# DualModeKeyboard.net
KiCad netlist of a schematic drawn in EasyEDA Pro
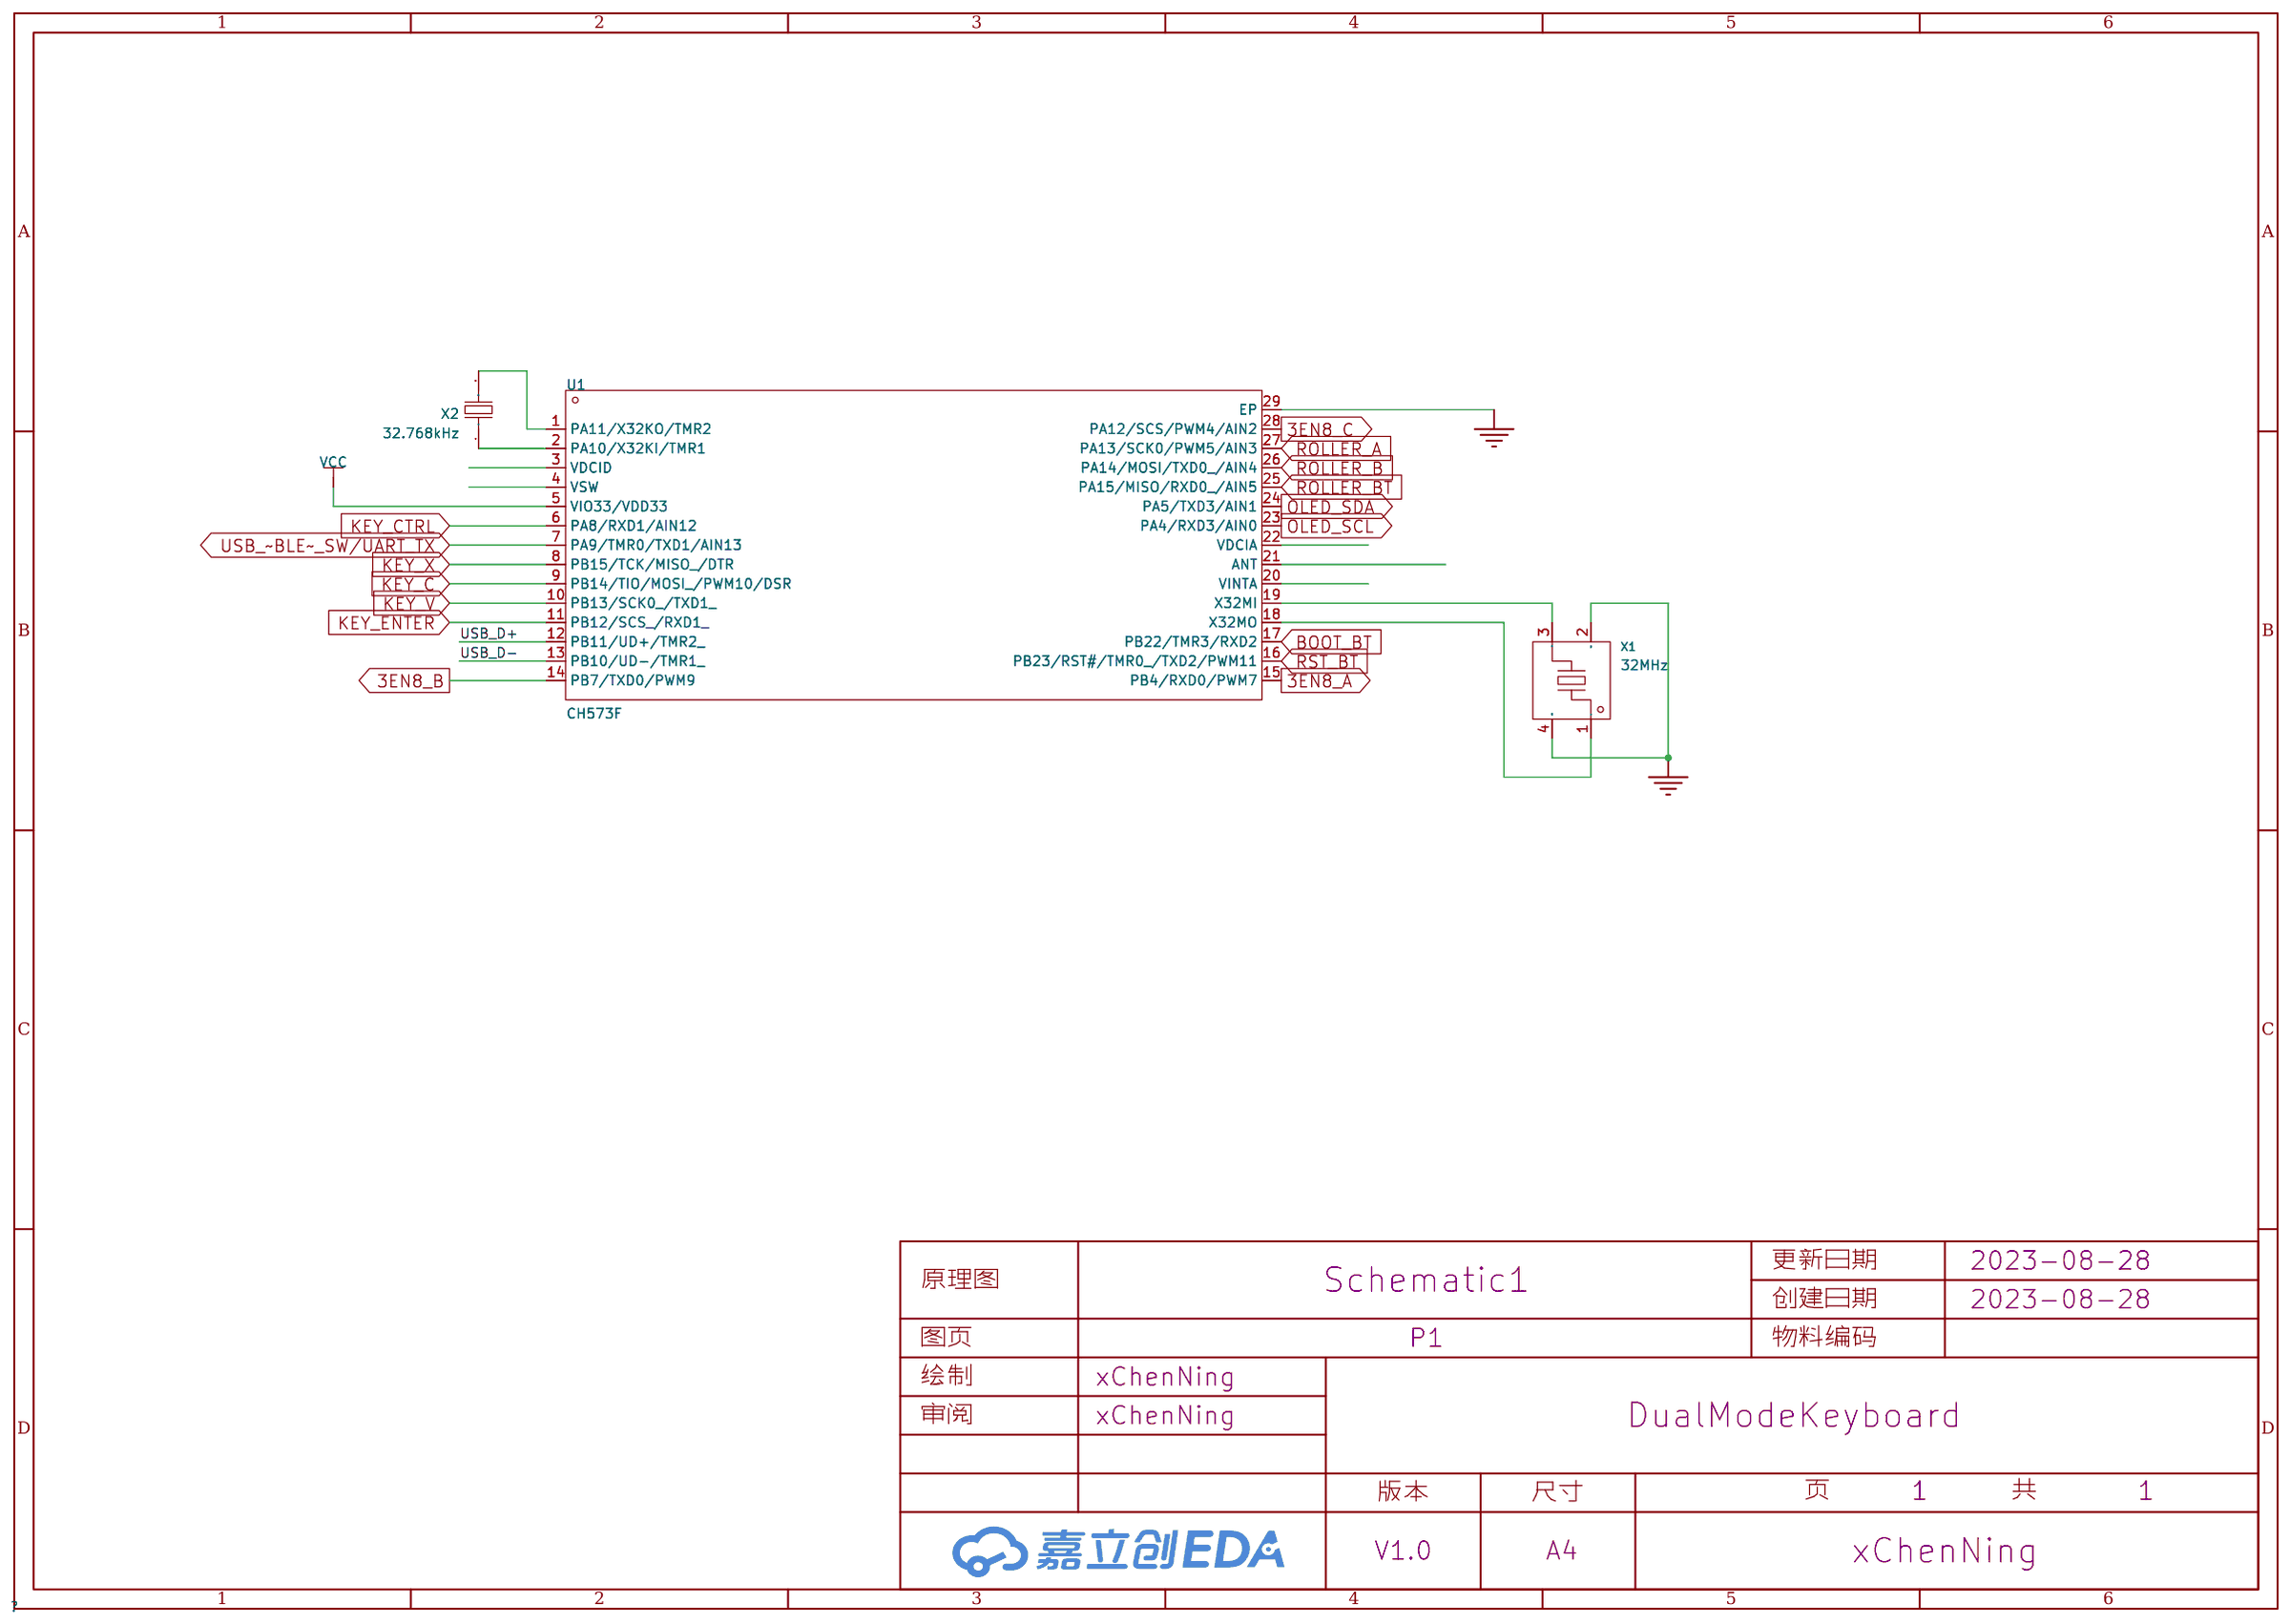
[diagram p0: schematic sheet]

(export (version "E")
  (design (tool "Eeschema 10.0.6"))
  (components
    (comp (ref "U1")
      (value "CH573F")
      (footprint "easyedapro:QFN-28_L4.0-W4.0-P0.40-BL-EP")
      (libsource (lib "easyedapro") (part "CH573F"))
    )
    (comp (ref "X1")
      (value "32MHz")
      (footprint "easyedapro:CRYSTAL-SMD_4P-L2.0-W1.6-BL")
      (description "频率:32MHz;频率公差:±10ppm;负载电容:8pF;")
      (fields (field (name "Manufacturer Part") "Q22FA1280002500") (field (name "Manufacturer") "EPSON(爱普生)"))
      (libsource (lib "easyedapro") (part "Q22FA12800025"))
    )
    (comp (ref "X2")
      (value "32.768kHz")
      (footprint "easyedapro:FC-135R_L3.2-W1.5")
      (description "频率:32.768kHz;频率公差:±20ppm;负载电容:12.5pF;")
      (fields (field (name "Manufacturer Part") "Q13FC1350000400") (field (name "Manufacturer") "EPSON(爱普生)"))
      (libsource (lib "easyedapro") (part "Q13FC1350000400"))
    )
  )
  (nets
    (net (code "1") (name "/USB_D+") (class "Default")
      (node (ref "U1") (pin "12") (pinfunction "PB11/UD+/TMR2__12") (pintype "input"))
    )
    (net (code "2") (name "/USB_D-") (class "Default")
      (node (ref "U1") (pin "13") (pinfunction "PB10/UD-/TMR1__13") (pintype "input"))
    )
    (net (code "3") (name "3EN8_A") (class "Default")
      (node (ref "U1") (pin "15") (pinfunction "PB4/RXD0/PWM7_15") (pintype "input"))
    )
    (net (code "4") (name "3EN8_B") (class "Default")
      (node (ref "U1") (pin "14") (pinfunction "PB7/TXD0/PWM9_14") (pintype "input"))
    )
    (net (code "5") (name "3EN8_C") (class "Default")
      (node (ref "U1") (pin "28") (pinfunction "PA12/SCS/PWM4/AIN2_28") (pintype "input"))
    )
    (net (code "6") (name "BOOT_BT") (class "Default")
      (node (ref "U1") (pin "17") (pinfunction "PB22/TMR3/RXD2_17") (pintype "input"))
    )
    (net (code "7") (name "GND") (class "Default")
      (node (ref "U1") (pin "29") (pinfunction "EP_29") (pintype "input"))
      (node (ref "X1") (pin "2") (pinfunction "GND_2") (pintype "input"))
      (node (ref "X1") (pin "4") (pinfunction "GND_4") (pintype "input"))
    )
    (net (code "8") (name "KEY_C") (class "Default")
      (node (ref "U1") (pin "9") (pinfunction "PB14/TIO/MOSI_/PWM10/DSR_9") (pintype "input"))
    )
    (net (code "9") (name "KEY_CTRL") (class "Default")
      (node (ref "U1") (pin "6") (pinfunction "PA8/RXD1/AIN12_6") (pintype "input"))
    )
    (net (code "10") (name "KEY_ENTER") (class "Default")
      (node (ref "U1") (pin "11") (pinfunction "PB12/SCS_/RXD1__11") (pintype "input"))
    )
    (net (code "11") (name "KEY_V") (class "Default")
      (node (ref "U1") (pin "10") (pinfunction "PB13/SCK0_/TXD1__10") (pintype "input"))
    )
    (net (code "12") (name "KEY_X") (class "Default")
      (node (ref "U1") (pin "8") (pinfunction "PB15/TCK/MISO_/DTR_8") (pintype "input"))
    )
    (net (code "13") (name "Net-(U1-PA10{slash}X32KI{slash}TMR1)") (class "Default")
      (node (ref "U1") (pin "2") (pinfunction "PA10/X32KI/TMR1_2") (pintype "input"))
      (node (ref "X2") (pin "1") (pinfunction "1_1") (pintype "input"))
    )
    (net (code "14") (name "Net-(U1-PA11{slash}X32KO{slash}TMR2)") (class "Default")
      (node (ref "U1") (pin "1") (pinfunction "PA11/X32KO/TMR2_1") (pintype "input"))
      (node (ref "X2") (pin "2") (pinfunction "2_2") (pintype "input"))
    )
    (net (code "15") (name "Net-(U1-X32MI)") (class "Default")
      (node (ref "U1") (pin "19") (pinfunction "X32MI_19") (pintype "input"))
      (node (ref "X1") (pin "3") (pinfunction "3_3") (pintype "input"))
    )
    (net (code "16") (name "Net-(U1-X32MO)") (class "Default")
      (node (ref "U1") (pin "18") (pinfunction "X32MO_18") (pintype "input"))
      (node (ref "X1") (pin "1") (pinfunction "1_1") (pintype "input"))
    )
    (net (code "17") (name "OLED_SCL") (class "Default")
      (node (ref "U1") (pin "23") (pinfunction "PA4/RXD3/AIN0_23") (pintype "input"))
    )
    (net (code "18") (name "OLED_SDA") (class "Default")
      (node (ref "U1") (pin "24") (pinfunction "PA5/TXD3/AIN1_24") (pintype "input"))
    )
    (net (code "19") (name "ROLLER_A") (class "Default")
      (node (ref "U1") (pin "27") (pinfunction "PA13/SCK0/PWM5/AIN3_27") (pintype "input"))
    )
    (net (code "20") (name "ROLLER_B") (class "Default")
      (node (ref "U1") (pin "26") (pinfunction "PA14/MOSI/TXD0_/AIN4_26") (pintype "input"))
    )
    (net (code "21") (name "ROLLER_BT") (class "Default")
      (node (ref "U1") (pin "25") (pinfunction "PA15/MISO/RXD0_/AIN5_25") (pintype "input"))
    )
    (net (code "22") (name "RST_BT") (class "Default")
      (node (ref "U1") (pin "16") (pinfunction "PB23/RST#/TMR0_/TXD2/PWM11_16") (pintype "input"))
    )
    (net (code "23") (name "USB_~BLE~_SW{slash}UART_TX") (class "Default")
      (node (ref "U1") (pin "7") (pinfunction "PA9/TMR0/TXD1/AIN13_7") (pintype "input"))
    )
    (net (code "24") (name "VCC") (class "Default")
      (node (ref "U1") (pin "5") (pinfunction "VIO33/VDD33_5") (pintype "input"))
    )
    (net (code "25") (name "unconnected-(U1-ANT-Pad21)") (class "Default")
      (node (ref "U1") (pin "21") (pinfunction "ANT_21") (pintype "input"))
    )
    (net (code "26") (name "unconnected-(U1-VDCIA-Pad22)") (class "Default")
      (node (ref "U1") (pin "22") (pinfunction "VDCIA_22") (pintype "input"))
    )
    (net (code "27") (name "unconnected-(U1-VDCID-Pad3)") (class "Default")
      (node (ref "U1") (pin "3") (pinfunction "VDCID_3") (pintype "input"))
    )
    (net (code "28") (name "unconnected-(U1-VINTA-Pad20)") (class "Default")
      (node (ref "U1") (pin "20") (pinfunction "VINTA_20") (pintype "input"))
    )
    (net (code "29") (name "unconnected-(U1-VSW-Pad4)") (class "Default")
      (node (ref "U1") (pin "4") (pinfunction "VSW_4") (pintype "input"))
    )
  )
)
